# Microcontroller.net
KiCad netlist of a schematic drawn in Altium Designer
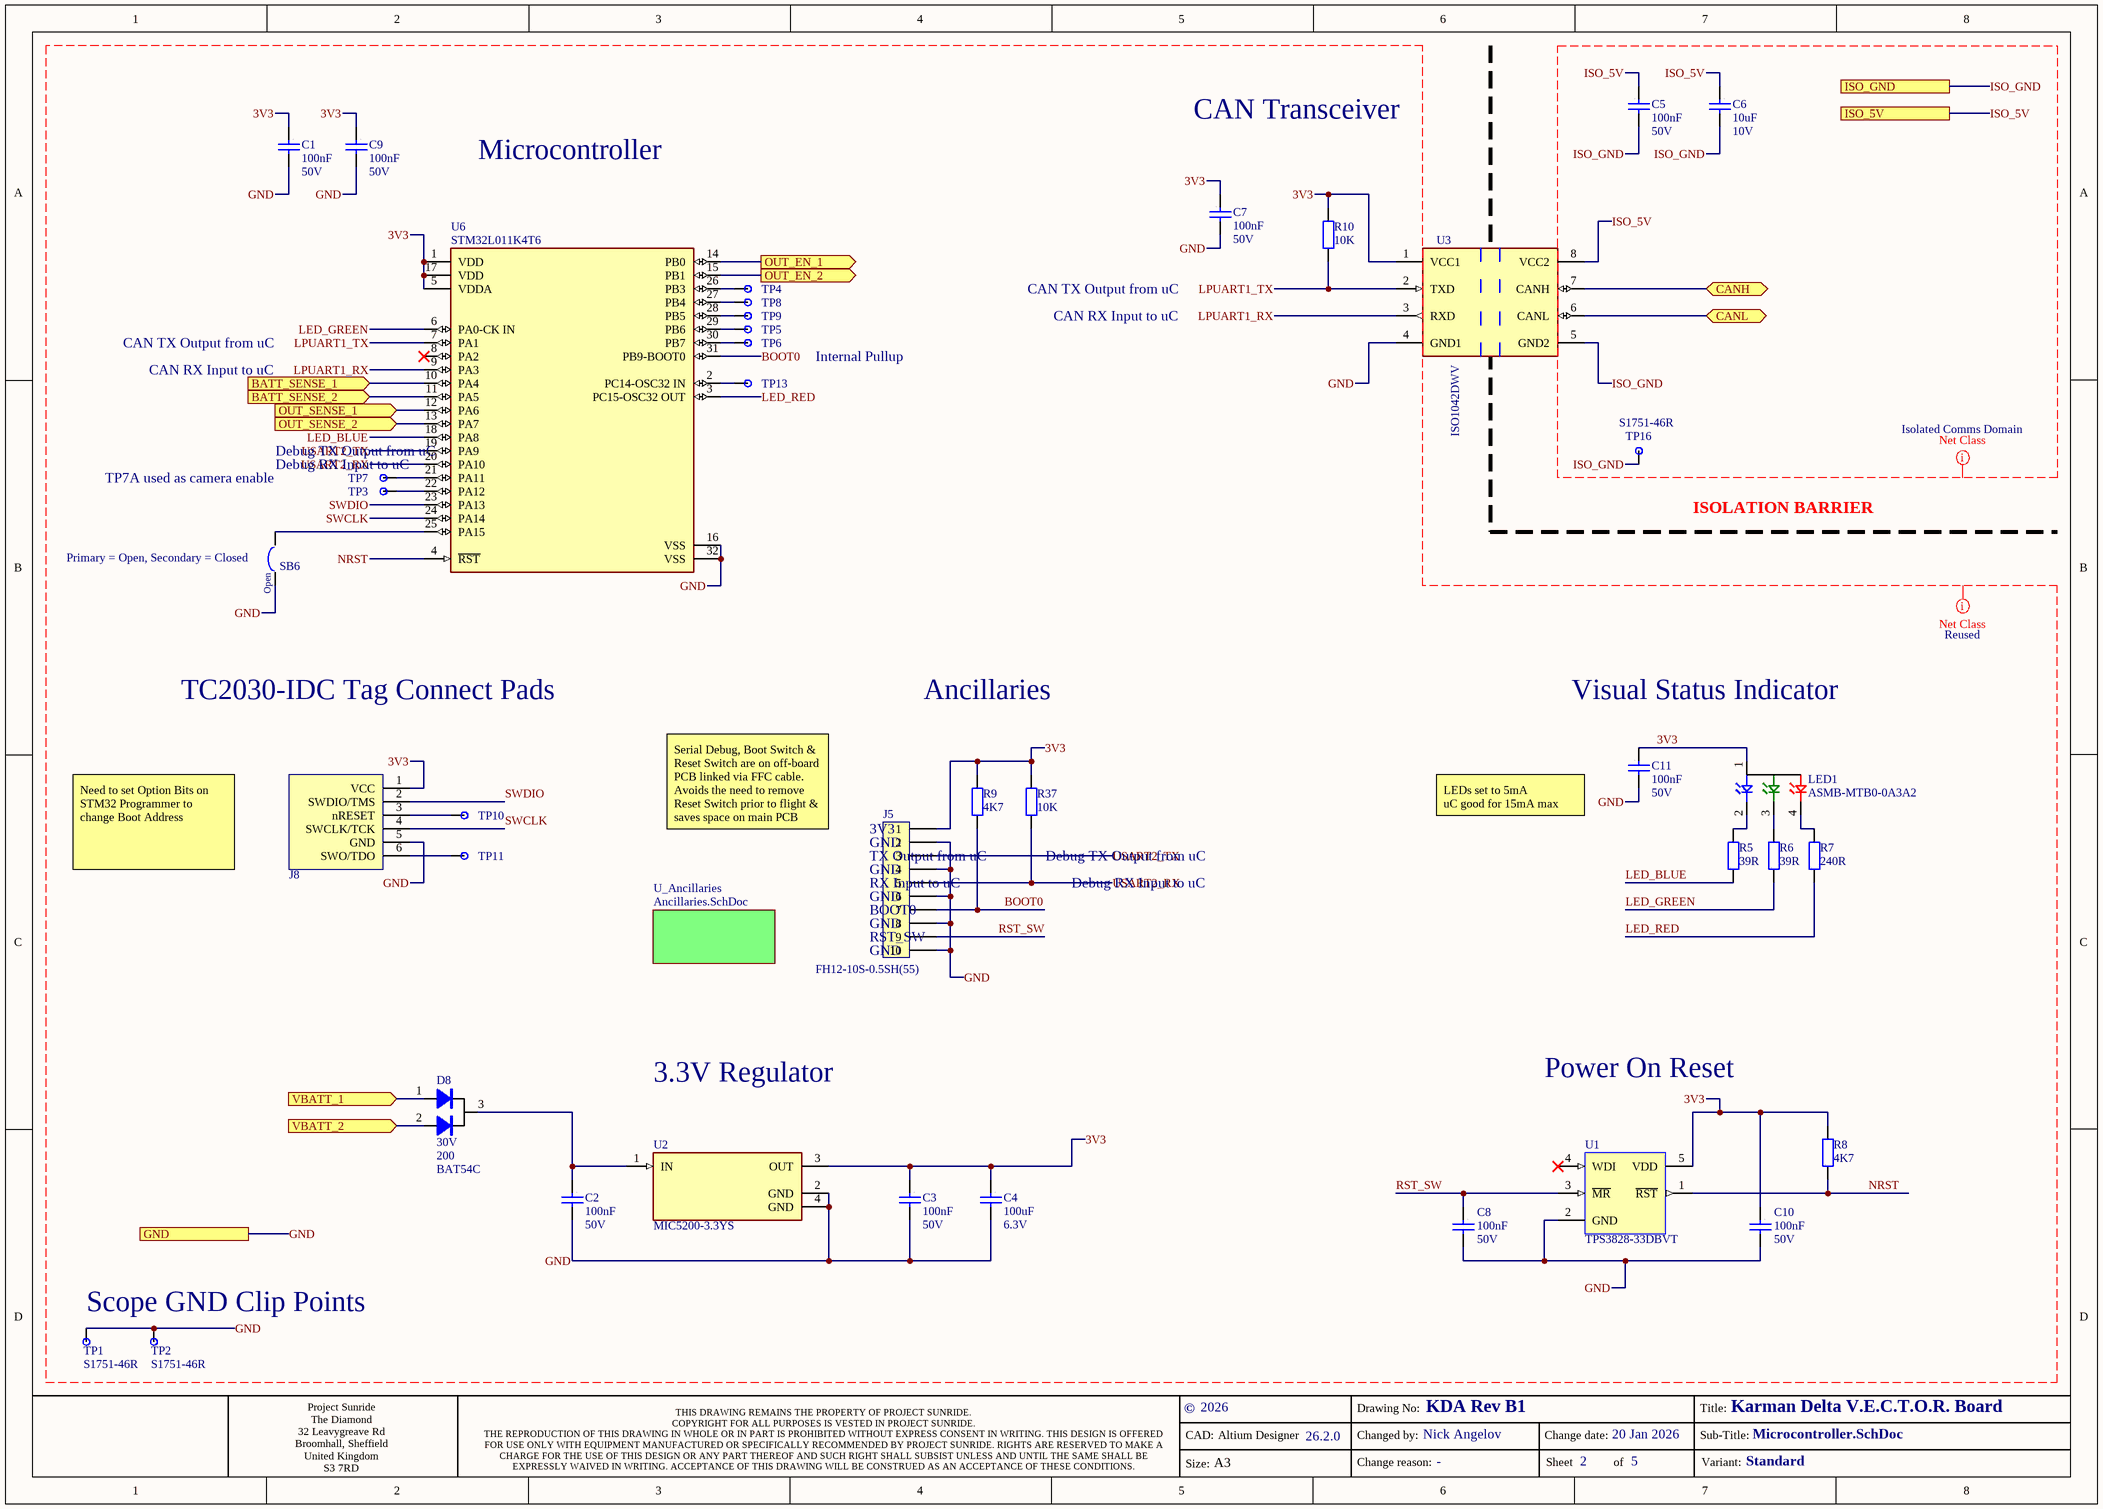
[diagram p0: Microcontroller.SchDoc]

(export (version "E")
  (design (tool "Eeschema 10.0.6"))
  (components
    (comp (ref "C1")
      (value "100nF")
      (footprint "CAPC1608X08L")
      (description "Capacitor MLC 100nF 50V X7R 10% CAPC1608X08M")
      (fields
        (field (name "VOLTAGE") "50V")
        (field (name "MANUFACTURER") "Murata")
        (field (name "MANUPARTNO") "GRM188R71H104KA93D")
      )
      (libsource (lib "Library") (part "CAP"))
    )
    (comp (ref "C2")
      (value "100nF")
      (footprint "CAPC1608X08L")
      (description "Capacitor MLC 100nF 50V X7R 10% CAPC1608X08M")
      (fields
        (field (name "VOLTAGE") "50V")
        (field (name "MANUFACTURER") "Murata")
        (field (name "MANUPARTNO") "GRM188R71H104KA93D")
      )
      (libsource (lib "Library") (part "CAP"))
    )
    (comp (ref "C3")
      (value "100nF")
      (footprint "CAPC1608X08L")
      (description "Capacitor MLC 100nF 50V X7R 10% CAPC1608X08M")
      (fields
        (field (name "VOLTAGE") "50V")
        (field (name "MANUFACTURER") "Murata")
        (field (name "MANUPARTNO") "GRM188R71H104KA93D")
      )
      (libsource (lib "Library") (part "CAP"))
    )
    (comp (ref "C4")
      (value "100uF")
      (footprint "CAPC2012X15L")
      (description "Capacitor MLC 100uF 6.3V X5R 20% CAPC2012X15M")
      (fields
        (field (name "VOLTAGE") "6.3V")
        (field (name "MANUPARTNO") "GRM21BR60J107ME15L")
        (field (name "TOLERANCE") "20%")
      )
      (libsource (lib "Library") (part "CAP"))
    )
    (comp (ref "C5")
      (value "100nF")
      (footprint "CAPC1608X08L")
      (description "Capacitor MLC 100nF 50V X7R 10% CAPC1608X08M")
      (fields
        (field (name "VOLTAGE") "50V")
        (field (name "MANUFACTURER") "Murata")
        (field (name "MANUPARTNO") "GRM188R71H104KA93D")
      )
      (libsource (lib "") (part "CAP_1"))
    )
    (comp (ref "C6")
      (value "10uF")
      (footprint "CAPC2012X15M")
      (description "Capacitor MLC 10uF10V X7R 10% CAPC2012X15M")
      (fields
        (field (name "VOLTAGE") "10V")
        (field (name "MANUFACTURER") "Murata")
        (field (name "MANUPARTNO") "GRM21BR71A106KE51L")
      )
      (libsource (lib "Library") (part "CAP"))
    )
    (comp (ref "C7")
      (value "100nF")
      (footprint "CAPC1608X08L")
      (description "Capacitor MLC 100nF 50V X7R 10% CAPC1608X08M")
      (fields
        (field (name "VOLTAGE") "50V")
        (field (name "MANUFACTURER") "Murata")
        (field (name "MANUPARTNO") "GRM188R71H104KA93D")
      )
      (libsource (lib "") (part "CAP_1"))
    )
    (comp (ref "C8")
      (value "100nF")
      (footprint "CAPC1608X08L")
      (description "Capacitor MLC 100nF 50V X7R 10% CAPC1608X08M")
      (fields
        (field (name "VOLTAGE") "50V")
        (field (name "MANUFACTURER") "Murata")
        (field (name "MANUPARTNO") "GRM188R71H104KA93D")
      )
      (libsource (lib "Library") (part "CAP"))
    )
    (comp (ref "C9")
      (value "100nF")
      (footprint "CAPC1608X08L")
      (description "Capacitor MLC 100nF 50V X7R 10% CAPC1608X08M")
      (fields
        (field (name "VOLTAGE") "50V")
        (field (name "MANUFACTURER") "Murata")
        (field (name "MANUPARTNO") "GRM188R71H104KA93D")
      )
      (libsource (lib "Library") (part "CAP"))
    )
    (comp (ref "C10")
      (value "100nF")
      (footprint "CAPC1608X08L")
      (description "Capacitor MLC 100nF 50V X7R 10% CAPC1608X08M")
      (fields
        (field (name "VOLTAGE") "50V")
        (field (name "MANUFACTURER") "Murata")
        (field (name "MANUPARTNO") "GRM188R71H104KA93D")
      )
      (libsource (lib "Library") (part "CAP"))
    )
    (comp (ref "C11")
      (value "100nF")
      (footprint "CAPC1608X08L")
      (description "Capacitor MLC 100nF 50V X7R 10% CAPC1608X08M")
      (fields
        (field (name "VOLTAGE") "50V")
        (field (name "MANUFACTURER") "Murata")
        (field (name "MANUPARTNO") "GRM188R71H104KA93D")
      )
      (libsource (lib "") (part "CAP_1"))
    )
    (comp (ref "D8")
      (value "*")
      (footprint "SOT95P237X112-3M")
      (description "Diode Schottky BAT54C SOT-23")
      (fields
        (field (name "VR (V)") "30V")
        (field (name "IF (MA)") "200")
        (field (name "MANUPARTNO") "BAT54C")
        (field (name "MANUFACTURER") "Fairchild")
      )
      (libsource (lib "Library") (part "DIODESOT23C"))
    )
    (comp (ref "J5")
      (value "Ancillaries")
      (footprint "FH12-10S-0_5SH")
      (description "Connector 10W FFC/FPC 0.5mm SM ZIF")
      (fields (field (name "MANUPARTNO") "FH12-10S-0.5SH(55)") (field (name "MANUFACTURER") "Hirose"))
      (libsource (lib "Library") (part "CON10"))
    )
    (comp (ref "J8")
      (value "TC2030-IDC Tag Connect Pads")
      (footprint "TC2030-IDC-NL")
      (description "TC2030 Tag Connect Programmer Connection - Non BOM part")
      (fields (field (name "MANUFACTURER") "Tag Connect"))
      (libsource (lib "Library") (part "TC2030-IDC"))
    )
    (comp (ref "LED1")
      (value "Visual Status Indicator")
      (footprint "ASMB-MTB0-0A3A2")
      (description "LED RGB, SMD, 2.4mm, 115 °")
      (fields (field (name "MANUPARTNO") "ASMB-MTB0-0A3A2") (field (name "MANUFACTURER") "Wurth"))
      (libsource (lib "Library") (part "LED_RGB"))
    )
    (comp (ref "R5")
      (value "39R")
      (footprint "RESC1608X06M")
      (description "Resistor 39R 1% 50V RESC1608X06M")
      (fields (field (name "VOLTAGE") "50V") (field (name "MANUFACTURER") "Multicomp"))
      (libsource (lib "") (part "RESISTOR_1"))
    )
    (comp (ref "R6")
      (value "39R")
      (footprint "RESC1608X06M")
      (description "Resistor 39R 1% 50V RESC1608X06M")
      (fields (field (name "VOLTAGE") "50V") (field (name "MANUFACTURER") "Multicomp"))
      (libsource (lib "") (part "RESISTOR_1"))
    )
    (comp (ref "R7")
      (value "240R")
      (footprint "RESC1608X06M")
      (description "Resistor 240R 1% 50V RESC1608X06M")
      (fields (field (name "VOLTAGE") "50V") (field (name "MANUFACTURER") "Multicomp"))
      (libsource (lib "") (part "RESISTOR_1"))
    )
    (comp (ref "R8")
      (value "4K7")
      (footprint "RESC1608X06L")
      (description "Resistor 4K7 1% 50V RESC1608X06M")
      (fields (field (name "VOLTAGE") "50V") (field (name "MANUFACTURER") "Multicomp"))
      (libsource (lib "") (part "RESISTOR_1"))
    )
    (comp (ref "R9")
      (value "4K7")
      (footprint "RESC1608X06L")
      (description "Resistor 4K7 1% 50V RESC1608X06M")
      (fields (field (name "VOLTAGE") "50V") (field (name "MANUFACTURER") "Multicomp"))
      (libsource (lib "") (part "RESISTOR_1"))
    )
    (comp (ref "R10")
      (value "10K")
      (footprint "RESC1608X06L")
      (description "SMD Chip Resistor, Thin Film, 10 kohm, 75 V, 0603 [1608 Metric], 100 mW, ± 0.1%, ERA3A Series")
      (fields (field (name "VOLTAGE") "75V") (field (name "MANUFACTURER") "Panasonic"))
      (libsource (lib "Library") (part "RESISTOR"))
    )
    (comp (ref "R37")
      (value "10K")
      (footprint "RESC1608X06L")
      (description "SMD Chip Resistor, Thin Film, 10 kohm, 75 V, 0603 [1608 Metric], 100 mW, ± 0.1%, ERA3A Series")
      (fields (field (name "VOLTAGE") "75V") (field (name "MANUFACTURER") "Panasonic"))
      (libsource (lib "Library") (part "RESISTOR"))
    )
    (comp (ref "SB6")
      (value "Primary = Open, Secondary = Closed")
      (footprint "0603SolderLinkOpen")
      (description "Solder Blob - Open 0603 SM pads")
      (libsource (lib "Library") (part "Solder Blob Open"))
    )
    (comp (ref "TP1")
      (value "GND")
      (footprint "S1751-46R")
      (description "PCB Test Point S1751 Series, Surface Mount")
      (fields (field (name "MANUPARTNO") "S1751-46R") (field (name "MANUFACTURER") "Harwin"))
      (libsource (lib "Library") (part "TP1-fitted"))
    )
    (comp (ref "TP2")
      (value "GND")
      (footprint "S1751-46R")
      (description "PCB Test Point S1751 Series, Surface Mount")
      (fields (field (name "MANUPARTNO") "S1751-46R") (field (name "MANUFACTURER") "Harwin"))
      (libsource (lib "Library") (part "TP1-fitted"))
    )
    (comp (ref "TP3")
      (value "TMS")
      (footprint "TP1")
      (description "Testpoint 1mm dia. Component side, no silk")
      (libsource (lib "Library") (part "TP1"))
    )
    (comp (ref "TP4")
      (value "TMS")
      (footprint "TP1")
      (description "Testpoint 1mm dia. Component side, no silk")
      (libsource (lib "Library") (part "TP1"))
    )
    (comp (ref "TP5")
      (value "TMS")
      (footprint "TP1")
      (description "Testpoint 1mm dia. Component side, no silk")
      (libsource (lib "Library") (part "TP1"))
    )
    (comp (ref "TP6")
      (value "TMS")
      (footprint "TP1")
      (description "Testpoint 1mm dia. Component side, no silk")
      (libsource (lib "Library") (part "TP1"))
    )
    (comp (ref "TP7")
      (value "TP7A used as camera enable")
      (footprint "TP1")
      (description "Testpoint 1mm dia. Component side, no silk")
      (libsource (lib "Library") (part "TP1"))
    )
    (comp (ref "TP8")
      (value "TMS")
      (footprint "TP1")
      (description "Testpoint 1mm dia. Component side, no silk")
      (libsource (lib "Library") (part "TP1"))
    )
    (comp (ref "TP9")
      (value "TMS")
      (footprint "TP1")
      (description "Testpoint 1mm dia. Component side, no silk")
      (libsource (lib "Library") (part "TP1"))
    )
    (comp (ref "TP10")
      (value "TMS")
      (footprint "TP1")
      (description "Testpoint 1mm dia. Component side, no silk")
      (libsource (lib "Library") (part "TP1"))
    )
    (comp (ref "TP11")
      (value "TMS")
      (footprint "TP1")
      (description "Testpoint 1mm dia. Component side, no silk")
      (libsource (lib "Library") (part "TP1"))
    )
    (comp (ref "TP13")
      (value "TMS")
      (footprint "TP1")
      (description "Testpoint 1mm dia. Component side, no silk")
      (libsource (lib "Library") (part "TP1"))
    )
    (comp (ref "TP16")
      (value "GND")
      (footprint "S1751-46R")
      (description "PCB Test Point S1751 Series, Surface Mount")
      (fields (field (name "MANUPARTNO") "S1751-46R") (field (name "MANUFACTURER") "Harwin"))
      (libsource (lib "Library") (part "TP1-fitted"))
    )
    (comp (ref "U1")
      (value "Power On Reset")
      (footprint "SOT95P280X145-5L")
      (description "IC Supply Voltage Monitor, 2.93V TPS3828-33DBVT SOT23-5")
      (fields (field (name "MANUPARTNO") "TPS3828-33DBVT") (field (name "MANUFACTURER") "Texas"))
      (libsource (lib "Library") (part "VSENSE5"))
    )
    (comp (ref "U2")
      (value "MIC5200-3.3YS")
      (footprint "FP-SOT223-3LD-PL-1-IPC_C")
      (description "IC REG LIN 3.3V 100MA SOT223-3")
      (libsource (lib "Altium Content Vault") (part "f5128a9f8ed94365bfd39dcb8083813"))
    )
    (comp (ref "U3")
      (value "CAN Transceiver")
      (footprint "FP-DWV0008A-IPC_C")
      (description "IC TRANSCEIVER FULL 1/1 8SOIC")
      (fields (field (name "MANUF PART NO") "ISO1042DWV"))
      (libsource (lib "Altium Content Vault") (part "909e5d76d32ef4d3bd4dfdc3f0018f8"))
    )
    (comp (ref "U6")
      (value "Microcontroller")
      (footprint "FP-LQFP32-5V-MFG")
      (description "IC MCU 32BIT 16KB FLASH 32LQFP")
      (fields
        (field (name "MANUFACTURER PART NUMBER") "STM32L011K4T6")
        (field (name "MANUFACTURER") "STMicroelectronics")
        (field (name "OCTOPART") "https://octopart.com/stm32l011k4t6-stmicroelectronics-71108062")
      )
      (libsource (lib "Altium Content Vault") (part "3cbf9028c7ade503566d0a55c35e94d"))
    )
  )
  (nets
    (net (code "1") (name "/3V3") (class "Default")
      (node (ref "C1") (pin "1") (pinfunction "1_1") (pintype "passive"))
      (node (ref "C10") (pin "1") (pinfunction "1_1") (pintype "passive"))
      (node (ref "C11") (pin "1") (pinfunction "1_1") (pintype "passive"))
      (node (ref "C3") (pin "1") (pinfunction "1_1") (pintype "passive"))
      (node (ref "C4") (pin "1") (pinfunction "1_1") (pintype "passive"))
      (node (ref "C7") (pin "1") (pinfunction "1_1") (pintype "passive"))
      (node (ref "C9") (pin "1") (pinfunction "1_1") (pintype "passive"))
      (node (ref "J5") (pin "1") (pinfunction "1_1") (pintype "passive"))
      (node (ref "J8") (pin "1") (pinfunction "VCC_1") (pintype "passive"))
      (node (ref "LED1") (pin "1") (pinfunction "A_1") (pintype "passive"))
      (node (ref "R10") (pin "2") (pinfunction "2_2") (pintype "passive"))
      (node (ref "R37") (pin "2") (pinfunction "2_2") (pintype "passive"))
      (node (ref "R8") (pin "2") (pinfunction "2_2") (pintype "passive"))
      (node (ref "R9") (pin "2") (pinfunction "2_2") (pintype "passive"))
      (node (ref "U1") (pin "5") (pinfunction "VDD_5") (pintype "power_in"))
      (node (ref "U2") (pin "3") (pinfunction "OUT_3") (pintype "power_in"))
      (node (ref "U3") (pin "1") (pinfunction "VCC1_1") (pintype "power_in"))
      (node (ref "U6") (pin "1") (pinfunction "VDD_1") (pintype "power_in"))
      (node (ref "U6") (pin "17") (pinfunction "VDD_17") (pintype "power_in"))
      (node (ref "U6") (pin "5") (pinfunction "VDDA_5") (pintype "power_in"))
    )
    (net (code "2") (name "/BATT_SENSE_1") (class "Default")
      (node (ref "U6") (pin "10") (pinfunction "PA4_10") (pintype "bidirectional"))
    )
    (net (code "3") (name "/BATT_SENSE_2") (class "Default")
      (node (ref "U6") (pin "11") (pinfunction "PA5_11") (pintype "bidirectional"))
    )
    (net (code "4") (name "/BOOT0") (class "Default")
      (node (ref "J5") (pin "7") (pinfunction "7_7") (pintype "passive"))
      (node (ref "R9") (pin "1") (pinfunction "1_1") (pintype "passive"))
      (node (ref "U6") (pin "31") (pinfunction "PB9-BOOT0_31") (pintype "bidirectional"))
    )
    (net (code "5") (name "/CANH") (class "Default")
      (node (ref "U3") (pin "7") (pinfunction "CANH_7") (pintype "bidirectional"))
    )
    (net (code "6") (name "/CANL") (class "Default")
      (node (ref "U3") (pin "6") (pinfunction "CANL_6") (pintype "bidirectional"))
    )
    (net (code "7") (name "/GND") (class "Default")
      (node (ref "C1") (pin "2") (pinfunction "2_2") (pintype "passive"))
      (node (ref "C10") (pin "2") (pinfunction "2_2") (pintype "passive"))
      (node (ref "C11") (pin "2") (pinfunction "2_2") (pintype "passive"))
      (node (ref "C2") (pin "2") (pinfunction "2_2") (pintype "passive"))
      (node (ref "C3") (pin "2") (pinfunction "2_2") (pintype "passive"))
      (node (ref "C4") (pin "2") (pinfunction "2_2") (pintype "passive"))
      (node (ref "C7") (pin "2") (pinfunction "2_2") (pintype "passive"))
      (node (ref "C8") (pin "2") (pinfunction "2_2") (pintype "passive"))
      (node (ref "C9") (pin "2") (pinfunction "2_2") (pintype "passive"))
      (node (ref "J5") (pin "10") (pinfunction "10_10") (pintype "passive"))
      (node (ref "J5") (pin "2") (pinfunction "2_2") (pintype "passive"))
      (node (ref "J5") (pin "4") (pinfunction "4_4") (pintype "passive"))
      (node (ref "J5") (pin "6") (pinfunction "6_6") (pintype "passive"))
      (node (ref "J5") (pin "8") (pinfunction "8_8") (pintype "passive"))
      (node (ref "J8") (pin "5") (pinfunction "GND_5") (pintype "passive"))
      (node (ref "SB6") (pin "1") (pinfunction "1_1") (pintype "passive"))
      (node (ref "TP1") (pin "1") (pintype "passive"))
      (node (ref "TP2") (pin "1") (pintype "passive"))
      (node (ref "U1") (pin "2") (pinfunction "GND_2") (pintype "passive"))
      (node (ref "U2") (pin "2") (pinfunction "GND_2") (pintype "power_in"))
      (node (ref "U2") (pin "4") (pinfunction "GND_4") (pintype "power_in"))
      (node (ref "U3") (pin "4") (pinfunction "GND1_4") (pintype "power_in"))
      (node (ref "U6") (pin "16") (pinfunction "VSS_16") (pintype "power_in"))
      (node (ref "U6") (pin "32") (pinfunction "VSS_32") (pintype "power_in"))
    )
    (net (code "8") (name "/ISO_5V") (class "Default")
      (node (ref "C5") (pin "1") (pinfunction "1_1") (pintype "passive"))
      (node (ref "C6") (pin "1") (pinfunction "1_1") (pintype "passive"))
      (node (ref "U3") (pin "8") (pinfunction "VCC2_8") (pintype "power_in"))
    )
    (net (code "9") (name "/ISO_GND") (class "Default")
      (node (ref "C5") (pin "2") (pinfunction "2_2") (pintype "passive"))
      (node (ref "C6") (pin "2") (pinfunction "2_2") (pintype "passive"))
      (node (ref "TP16") (pin "1") (pintype "passive"))
      (node (ref "U3") (pin "5") (pinfunction "GND2_5") (pintype "power_in"))
    )
    (net (code "10") (name "/LED_BLUE") (class "Default")
      (node (ref "R5") (pin "1") (pinfunction "1_1") (pintype "passive"))
      (node (ref "U6") (pin "18") (pinfunction "PA8_18") (pintype "bidirectional"))
    )
    (net (code "11") (name "/LED_GREEN") (class "Default")
      (node (ref "R6") (pin "1") (pinfunction "1_1") (pintype "passive"))
      (node (ref "U6") (pin "6") (pinfunction "PA0-CK_IN_6") (pintype "bidirectional"))
    )
    (net (code "12") (name "/LED_RED") (class "Default")
      (node (ref "R7") (pin "1") (pinfunction "1_1") (pintype "passive"))
      (node (ref "U6") (pin "3") (pinfunction "PC15-OSC32_OUT_3") (pintype "bidirectional"))
    )
    (net (code "13") (name "/LPUART1_RX") (class "Default")
      (node (ref "U3") (pin "3") (pinfunction "RXD_3") (pintype "output"))
      (node (ref "U6") (pin "9") (pinfunction "PA3_9") (pintype "bidirectional"))
    )
    (net (code "14") (name "/LPUART1_TX") (class "Default")
      (node (ref "R10") (pin "1") (pinfunction "1_1") (pintype "passive"))
      (node (ref "U3") (pin "2") (pinfunction "TXD_2") (pintype "input"))
      (node (ref "U6") (pin "7") (pinfunction "PA1_7") (pintype "bidirectional"))
    )
    (net (code "15") (name "/NRST") (class "Default")
      (node (ref "R8") (pin "1") (pinfunction "1_1") (pintype "passive"))
      (node (ref "U1") (pin "1") (pinfunction "RST_1") (pintype "output"))
      (node (ref "U6") (pin "4") (pinfunction "~{RST}_4") (pintype "input"))
    )
    (net (code "16") (name "/OUT_EN_1") (class "Default")
      (node (ref "U6") (pin "14") (pinfunction "PB0_14") (pintype "bidirectional"))
    )
    (net (code "17") (name "/OUT_EN_2") (class "Default")
      (node (ref "U6") (pin "15") (pinfunction "PB1_15") (pintype "bidirectional"))
    )
    (net (code "18") (name "/OUT_SENSE_1") (class "Default")
      (node (ref "U6") (pin "12") (pinfunction "PA6_12") (pintype "bidirectional"))
    )
    (net (code "19") (name "/OUT_SENSE_2") (class "Default")
      (node (ref "U6") (pin "13") (pinfunction "PA7_13") (pintype "bidirectional"))
    )
    (net (code "20") (name "/RST_SW") (class "Default")
      (node (ref "C8") (pin "1") (pinfunction "1_1") (pintype "passive"))
      (node (ref "J5") (pin "9") (pinfunction "9_9") (pintype "passive"))
      (node (ref "U1") (pin "3") (pinfunction "MR_3") (pintype "input"))
    )
    (net (code "21") (name "/SWCLK") (class "Default")
      (node (ref "J8") (pin "4") (pinfunction "SWCLK/TCK_4") (pintype "passive"))
      (node (ref "U6") (pin "24") (pinfunction "PA14_24") (pintype "bidirectional"))
    )
    (net (code "22") (name "/SWDIO") (class "Default")
      (node (ref "J8") (pin "2") (pinfunction "SWDIO/TMS_2") (pintype "passive"))
      (node (ref "U6") (pin "23") (pinfunction "PA13_23") (pintype "bidirectional"))
    )
    (net (code "23") (name "/USART2_RX") (class "Default")
      (node (ref "J5") (pin "5") (pinfunction "5_5") (pintype "passive"))
      (node (ref "R37") (pin "1") (pinfunction "1_1") (pintype "passive"))
      (node (ref "U6") (pin "20") (pinfunction "PA10_20") (pintype "bidirectional"))
    )
    (net (code "24") (name "/USART2_TX") (class "Default")
      (node (ref "J5") (pin "3") (pinfunction "3_3") (pintype "passive"))
      (node (ref "U6") (pin "19") (pinfunction "PA9_19") (pintype "bidirectional"))
    )
    (net (code "25") (name "/VBATT_1") (class "Default")
      (node (ref "D8") (pin "1") (pinfunction "1_1") (pintype "passive"))
    )
    (net (code "26") (name "/VBATT_2") (class "Default")
      (node (ref "D8") (pin "2") (pinfunction "2_2") (pintype "passive"))
    )
    (net (code "27") (name "Net-(J8-SWO{slash}TDO)") (class "Default")
      (node (ref "J8") (pin "6") (pinfunction "SWO/TDO_6") (pintype "passive"))
      (node (ref "TP11") (pin "1") (pintype "passive"))
    )
    (net (code "28") (name "Net-(J8-nRESET)") (class "Default")
      (node (ref "J8") (pin "3") (pinfunction "nRESET_3") (pintype "passive"))
      (node (ref "TP10") (pin "1") (pintype "passive"))
    )
    (net (code "29") (name "Net-(LED1-B)") (class "Default")
      (node (ref "LED1") (pin "2") (pinfunction "B_2") (pintype "passive"))
      (node (ref "R5") (pin "2") (pinfunction "2_2") (pintype "passive"))
    )
    (net (code "30") (name "Net-(LED1-G)") (class "Default")
      (node (ref "LED1") (pin "3") (pinfunction "G_3") (pintype "passive"))
      (node (ref "R6") (pin "2") (pinfunction "2_2") (pintype "passive"))
    )
    (net (code "31") (name "Net-(LED1-R)") (class "Default")
      (node (ref "LED1") (pin "4") (pinfunction "R_4") (pintype "passive"))
      (node (ref "R7") (pin "2") (pinfunction "2_2") (pintype "passive"))
    )
    (net (code "32") (name "Net-(U2-IN)") (class "Default")
      (node (ref "C2") (pin "1") (pinfunction "1_1") (pintype "passive"))
      (node (ref "D8") (pin "3") (pinfunction "3_3") (pintype "passive"))
      (node (ref "U2") (pin "1") (pinfunction "IN_1") (pintype "input"))
    )
    (net (code "33") (name "Net-(U6-PA11)") (class "Default")
      (node (ref "TP7") (pin "1") (pintype "passive"))
      (node (ref "U6") (pin "21") (pinfunction "PA11_21") (pintype "bidirectional"))
    )
    (net (code "34") (name "Net-(U6-PA12)") (class "Default")
      (node (ref "TP3") (pin "1") (pintype "passive"))
      (node (ref "U6") (pin "22") (pinfunction "PA12_22") (pintype "bidirectional"))
    )
    (net (code "35") (name "Net-(U6-PA15)") (class "Default")
      (node (ref "SB6") (pin "2") (pinfunction "2_2") (pintype "passive"))
      (node (ref "U6") (pin "25") (pinfunction "PA15_25") (pintype "bidirectional"))
    )
    (net (code "36") (name "Net-(U6-PB3)") (class "Default")
      (node (ref "TP4") (pin "1") (pintype "passive"))
      (node (ref "U6") (pin "26") (pinfunction "PB3_26") (pintype "bidirectional"))
    )
    (net (code "37") (name "Net-(U6-PB4)") (class "Default")
      (node (ref "TP8") (pin "1") (pintype "passive"))
      (node (ref "U6") (pin "27") (pinfunction "PB4_27") (pintype "bidirectional"))
    )
    (net (code "38") (name "Net-(U6-PB5)") (class "Default")
      (node (ref "TP9") (pin "1") (pintype "passive"))
      (node (ref "U6") (pin "28") (pinfunction "PB5_28") (pintype "bidirectional"))
    )
    (net (code "39") (name "Net-(U6-PB6)") (class "Default")
      (node (ref "TP5") (pin "1") (pintype "passive"))
      (node (ref "U6") (pin "29") (pinfunction "PB6_29") (pintype "bidirectional"))
    )
    (net (code "40") (name "Net-(U6-PB7)") (class "Default")
      (node (ref "TP6") (pin "1") (pintype "passive"))
      (node (ref "U6") (pin "30") (pinfunction "PB7_30") (pintype "bidirectional"))
    )
    (net (code "41") (name "Net-(U6-PC14-OSC32_IN)") (class "Default")
      (node (ref "TP13") (pin "1") (pintype "passive"))
      (node (ref "U6") (pin "2") (pinfunction "PC14-OSC32_IN_2") (pintype "bidirectional"))
    )
    (net (code "42") (name "unconnected-(U1-WDI-Pad4)") (class "Default")
      (node (ref "U1") (pin "4") (pinfunction "WDI_4") (pintype "input+no_connect"))
    )
    (net (code "43") (name "unconnected-(U6-PA2-Pad8)") (class "Default")
      (node (ref "U6") (pin "8") (pinfunction "PA2_8") (pintype "bidirectional+no_connect"))
    )
  )
)
